# FPGA_IO_3.net
KiCad netlist of a schematic drawn in Altium Designer
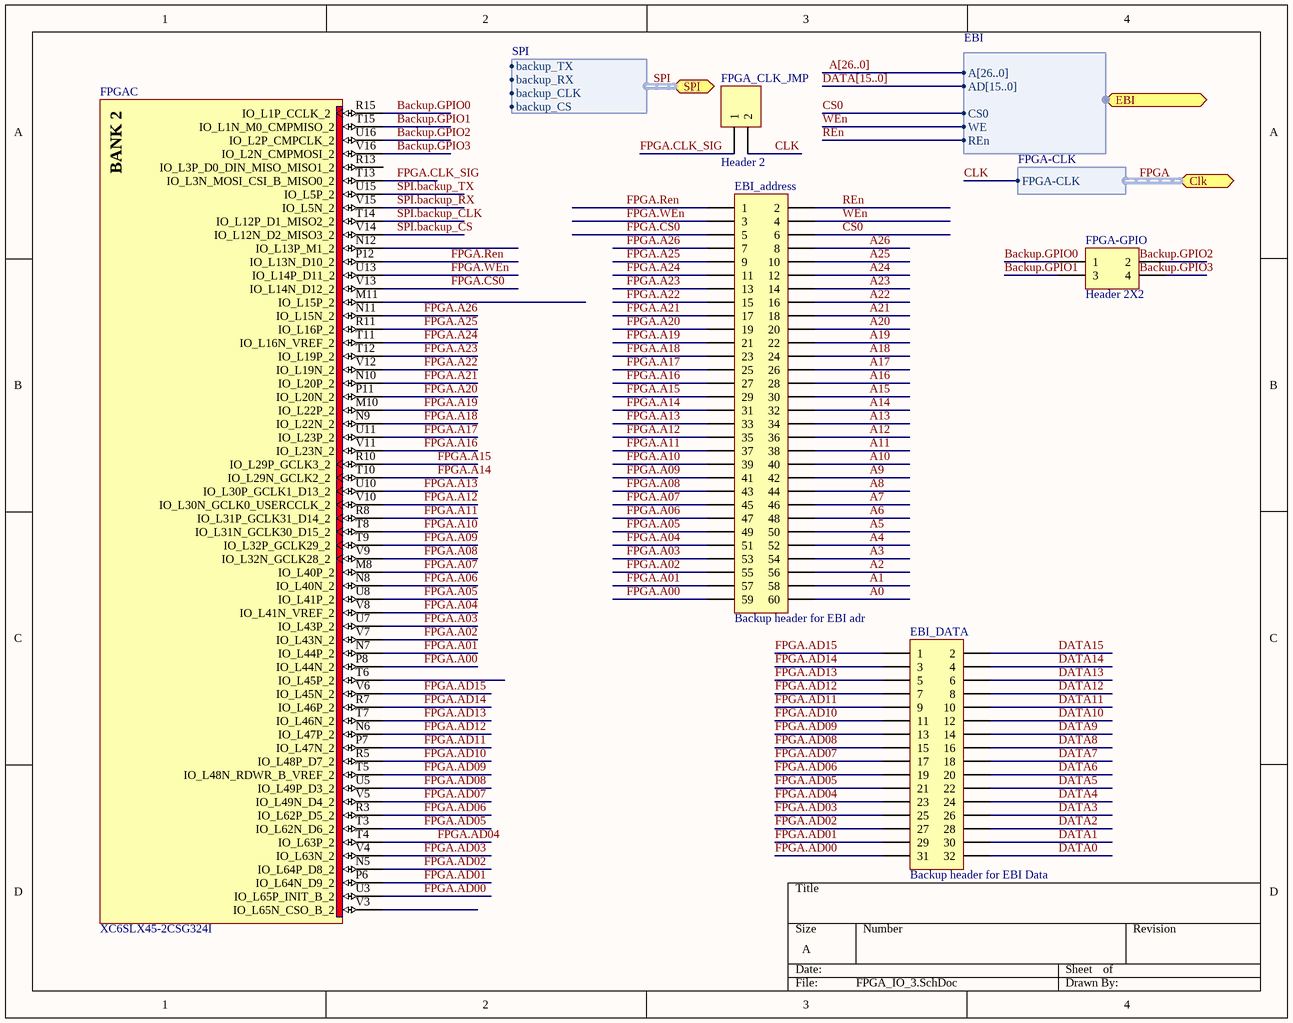
[diagram p0: FPGA_IO_3.SchDoc]

(export (version "E")
  (design (tool "Eeschema 10.0.6"))
  (components
    (comp (ref "EBI_address")
      (value "Backup header for EBI adr")
      (footprint "HDR2X30")
      (description "Header, 30-Pin, Dual row")
      (fields (field (name "PUBLISHER") "Altium Limited"))
      (libsource (lib "Miscellaneous Connectors") (part "Header 30X2"))
    )
    (comp (ref "EBI_DATA")
      (value "Backup header for EBI Data")
      (footprint "HDR2X16")
      (description "Header, 16-Pin, Dual row")
      (fields (field (name "PUBLISHER") "Altium Limited"))
      (libsource (lib "Miscellaneous Connectors") (part "Header 16X2"))
    )
    (comp (ref "FPGA")
      (value "XC6SLX45-2CSG324I")
      (footprint "CSG324")
      (libsource (lib "Altium Content Vault") (part "CMP-0067-00402-1"))
    )
    (comp (ref "FPGA-GPIO")
      (value "Header 2X2")
      (footprint "HDR2X2")
      (description "Header, 2-Pin, Dual row")
      (fields (field (name "PUBLISHER") "Altium Limited"))
      (libsource (lib "Miscellaneous Connectors") (part "Header 2X2"))
    )
    (comp (ref "FPGA_CLK_JMP")
      (value "Header 2")
      (footprint "HDR1X2")
      (description "Header, 2-Pin")
      (fields (field (name "PUBLISHER") "Altium Limited"))
      (libsource (lib "Miscellaneous Connectors") (part "Header 2"))
    )
  )
  (nets
    (net (code "4") (name "/A0") (class "Default")
      (node (ref "EBI_address") (pin "60") (pinfunction "60_60") (pintype "passive"))
    )
    (net (code "5") (name "/A1") (class "Default")
      (node (ref "EBI_address") (pin "58") (pinfunction "58_58") (pintype "passive"))
    )
    (net (code "6") (name "/A2") (class "Default")
      (node (ref "EBI_address") (pin "56") (pinfunction "56_56") (pintype "passive"))
    )
    (net (code "7") (name "/A3") (class "Default")
      (node (ref "EBI_address") (pin "54") (pinfunction "54_54") (pintype "passive"))
    )
    (net (code "8") (name "/A4") (class "Default")
      (node (ref "EBI_address") (pin "52") (pinfunction "52_52") (pintype "passive"))
    )
    (net (code "9") (name "/A5") (class "Default")
      (node (ref "EBI_address") (pin "50") (pinfunction "50_50") (pintype "passive"))
    )
    (net (code "10") (name "/A6") (class "Default")
      (node (ref "EBI_address") (pin "48") (pinfunction "48_48") (pintype "passive"))
    )
    (net (code "11") (name "/A7") (class "Default")
      (node (ref "EBI_address") (pin "46") (pinfunction "46_46") (pintype "passive"))
    )
    (net (code "12") (name "/A8") (class "Default")
      (node (ref "EBI_address") (pin "44") (pinfunction "44_44") (pintype "passive"))
    )
    (net (code "13") (name "/A9") (class "Default")
      (node (ref "EBI_address") (pin "42") (pinfunction "42_42") (pintype "passive"))
    )
    (net (code "14") (name "/A10") (class "Default")
      (node (ref "EBI_address") (pin "40") (pinfunction "40_40") (pintype "passive"))
    )
    (net (code "15") (name "/A11") (class "Default")
      (node (ref "EBI_address") (pin "38") (pinfunction "38_38") (pintype "passive"))
    )
    (net (code "16") (name "/A12") (class "Default")
      (node (ref "EBI_address") (pin "36") (pinfunction "36_36") (pintype "passive"))
    )
    (net (code "17") (name "/A13") (class "Default")
      (node (ref "EBI_address") (pin "34") (pinfunction "34_34") (pintype "passive"))
    )
    (net (code "18") (name "/A14") (class "Default")
      (node (ref "EBI_address") (pin "32") (pinfunction "32_32") (pintype "passive"))
    )
    (net (code "19") (name "/A15") (class "Default")
      (node (ref "EBI_address") (pin "30") (pinfunction "30_30") (pintype "passive"))
    )
    (net (code "20") (name "/A16") (class "Default")
      (node (ref "EBI_address") (pin "28") (pinfunction "28_28") (pintype "passive"))
    )
    (net (code "21") (name "/A17") (class "Default")
      (node (ref "EBI_address") (pin "26") (pinfunction "26_26") (pintype "passive"))
    )
    (net (code "22") (name "/A18") (class "Default")
      (node (ref "EBI_address") (pin "24") (pinfunction "24_24") (pintype "passive"))
    )
    (net (code "23") (name "/A19") (class "Default")
      (node (ref "EBI_address") (pin "22") (pinfunction "22_22") (pintype "passive"))
    )
    (net (code "24") (name "/A20") (class "Default")
      (node (ref "EBI_address") (pin "20") (pinfunction "20_20") (pintype "passive"))
    )
    (net (code "25") (name "/A21") (class "Default")
      (node (ref "EBI_address") (pin "18") (pinfunction "18_18") (pintype "passive"))
    )
    (net (code "26") (name "/A22") (class "Default")
      (node (ref "EBI_address") (pin "16") (pinfunction "16_16") (pintype "passive"))
    )
    (net (code "27") (name "/A23") (class "Default")
      (node (ref "EBI_address") (pin "14") (pinfunction "14_14") (pintype "passive"))
    )
    (net (code "28") (name "/A24") (class "Default")
      (node (ref "EBI_address") (pin "12") (pinfunction "12_12") (pintype "passive"))
    )
    (net (code "29") (name "/A25") (class "Default")
      (node (ref "EBI_address") (pin "10") (pinfunction "10_10") (pintype "passive"))
    )
    (net (code "30") (name "/A26") (class "Default")
      (node (ref "EBI_address") (pin "8") (pinfunction "8_8") (pintype "passive"))
    )
    (net (code "31") (name "/Backup.GPIO0") (class "Default")
      (node (ref "FPGA") (pin "R15") (pinfunction "IO_L1P_CCLK_2_R15") (pintype "bidirectional"))
      (node (ref "FPGA-GPIO") (pin "1") (pinfunction "1_1") (pintype "passive"))
    )
    (net (code "32") (name "/Backup.GPIO1") (class "Default")
      (node (ref "FPGA") (pin "T15") (pinfunction "IO_L1N_M0_CMPMISO_2_T15") (pintype "bidirectional"))
      (node (ref "FPGA-GPIO") (pin "3") (pinfunction "3_3") (pintype "passive"))
    )
    (net (code "33") (name "/Backup.GPIO2") (class "Default")
      (node (ref "FPGA") (pin "U16") (pinfunction "IO_L2P_CMPCLK_2_U16") (pintype "bidirectional"))
    )
    (net (code "34") (name "/Backup.GPIO3") (class "Default")
      (node (ref "FPGA") (pin "V16") (pinfunction "IO_L2N_CMPMOSI_2_V16") (pintype "bidirectional"))
    )
    (net (code "35") (name "/CLK") (class "Default")
      (node (ref "FPGA_CLK_JMP") (pin "2") (pinfunction "2_2") (pintype "passive"))
    )
    (net (code "36") (name "/CS0") (class "Default")
      (node (ref "EBI_address") (pin "6") (pinfunction "6_6") (pintype "passive"))
    )
    (net (code "37") (name "/DATA0") (class "Default")
      (node (ref "EBI_DATA") (pin "32") (pinfunction "32_32") (pintype "passive"))
    )
    (net (code "38") (name "/DATA1") (class "Default")
      (node (ref "EBI_DATA") (pin "30") (pinfunction "30_30") (pintype "passive"))
    )
    (net (code "39") (name "/DATA2") (class "Default")
      (node (ref "EBI_DATA") (pin "28") (pinfunction "28_28") (pintype "passive"))
    )
    (net (code "40") (name "/DATA3") (class "Default")
      (node (ref "EBI_DATA") (pin "26") (pinfunction "26_26") (pintype "passive"))
    )
    (net (code "41") (name "/DATA4") (class "Default")
      (node (ref "EBI_DATA") (pin "24") (pinfunction "24_24") (pintype "passive"))
    )
    (net (code "42") (name "/DATA5") (class "Default")
      (node (ref "EBI_DATA") (pin "22") (pinfunction "22_22") (pintype "passive"))
    )
    (net (code "43") (name "/DATA6") (class "Default")
      (node (ref "EBI_DATA") (pin "20") (pinfunction "20_20") (pintype "passive"))
    )
    (net (code "44") (name "/DATA7") (class "Default")
      (node (ref "EBI_DATA") (pin "18") (pinfunction "18_18") (pintype "passive"))
    )
    (net (code "45") (name "/DATA8") (class "Default")
      (node (ref "EBI_DATA") (pin "16") (pinfunction "16_16") (pintype "passive"))
    )
    (net (code "46") (name "/DATA9") (class "Default")
      (node (ref "EBI_DATA") (pin "14") (pinfunction "14_14") (pintype "passive"))
    )
    (net (code "47") (name "/DATA10") (class "Default")
      (node (ref "EBI_DATA") (pin "12") (pinfunction "12_12") (pintype "passive"))
    )
    (net (code "48") (name "/DATA11") (class "Default")
      (node (ref "EBI_DATA") (pin "10") (pinfunction "10_10") (pintype "passive"))
    )
    (net (code "49") (name "/DATA12") (class "Default")
      (node (ref "EBI_DATA") (pin "8") (pinfunction "8_8") (pintype "passive"))
    )
    (net (code "50") (name "/DATA13") (class "Default")
      (node (ref "EBI_DATA") (pin "6") (pinfunction "6_6") (pintype "passive"))
    )
    (net (code "51") (name "/DATA14") (class "Default")
      (node (ref "EBI_DATA") (pin "4") (pinfunction "4_4") (pintype "passive"))
    )
    (net (code "52") (name "/DATA15") (class "Default")
      (node (ref "EBI_DATA") (pin "2") (pinfunction "2_2") (pintype "passive"))
    )
    (net (code "55") (name "/FPGA.A00") (class "Default")
      (node (ref "EBI_address") (pin "59") (pinfunction "59_59") (pintype "passive"))
      (node (ref "FPGA") (pin "P8") (pinfunction "IO_L44N_2_P8") (pintype "bidirectional"))
    )
    (net (code "56") (name "/FPGA.A01") (class "Default")
      (node (ref "EBI_address") (pin "57") (pinfunction "57_57") (pintype "passive"))
      (node (ref "FPGA") (pin "N7") (pinfunction "IO_L44P_2_N7") (pintype "bidirectional"))
    )
    (net (code "57") (name "/FPGA.A02") (class "Default")
      (node (ref "EBI_address") (pin "55") (pinfunction "55_55") (pintype "passive"))
      (node (ref "FPGA") (pin "V7") (pinfunction "IO_L43N_2_V7") (pintype "bidirectional"))
    )
    (net (code "58") (name "/FPGA.A03") (class "Default")
      (node (ref "EBI_address") (pin "53") (pinfunction "53_53") (pintype "passive"))
      (node (ref "FPGA") (pin "U7") (pinfunction "IO_L43P_2_U7") (pintype "bidirectional"))
    )
    (net (code "59") (name "/FPGA.A04") (class "Default")
      (node (ref "EBI_address") (pin "51") (pinfunction "51_51") (pintype "passive"))
      (node (ref "FPGA") (pin "V8") (pinfunction "IO_L41N_VREF_2_V8") (pintype "bidirectional"))
    )
    (net (code "60") (name "/FPGA.A05") (class "Default")
      (node (ref "EBI_address") (pin "49") (pinfunction "49_49") (pintype "passive"))
      (node (ref "FPGA") (pin "U8") (pinfunction "IO_L41P_2_U8") (pintype "bidirectional"))
    )
    (net (code "61") (name "/FPGA.A06") (class "Default")
      (node (ref "EBI_address") (pin "47") (pinfunction "47_47") (pintype "passive"))
      (node (ref "FPGA") (pin "N8") (pinfunction "IO_L40N_2_N8") (pintype "bidirectional"))
    )
    (net (code "62") (name "/FPGA.A07") (class "Default")
      (node (ref "EBI_address") (pin "45") (pinfunction "45_45") (pintype "passive"))
      (node (ref "FPGA") (pin "M8") (pinfunction "IO_L40P_2_M8") (pintype "bidirectional"))
    )
    (net (code "63") (name "/FPGA.A08") (class "Default")
      (node (ref "EBI_address") (pin "43") (pinfunction "43_43") (pintype "passive"))
      (node (ref "FPGA") (pin "V9") (pinfunction "IO_L32N_GCLK28_2_V9") (pintype "bidirectional"))
    )
    (net (code "64") (name "/FPGA.A09") (class "Default")
      (node (ref "EBI_address") (pin "41") (pinfunction "41_41") (pintype "passive"))
      (node (ref "FPGA") (pin "T9") (pinfunction "IO_L32P_GCLK29_2_T9") (pintype "bidirectional"))
    )
    (net (code "65") (name "/FPGA.A10") (class "Default")
      (node (ref "EBI_address") (pin "39") (pinfunction "39_39") (pintype "passive"))
      (node (ref "FPGA") (pin "T8") (pinfunction "IO_L31N_GCLK30_D15_2_T8") (pintype "bidirectional"))
    )
    (net (code "66") (name "/FPGA.A11") (class "Default")
      (node (ref "EBI_address") (pin "37") (pinfunction "37_37") (pintype "passive"))
      (node (ref "FPGA") (pin "R8") (pinfunction "IO_L31P_GCLK31_D14_2_R8") (pintype "bidirectional"))
    )
    (net (code "67") (name "/FPGA.A12") (class "Default")
      (node (ref "EBI_address") (pin "35") (pinfunction "35_35") (pintype "passive"))
      (node (ref "FPGA") (pin "V10") (pinfunction "IO_L30N_GCLK0_USERCCLK_2_V10") (pintype "bidirectional"))
    )
    (net (code "68") (name "/FPGA.A13") (class "Default")
      (node (ref "EBI_address") (pin "33") (pinfunction "33_33") (pintype "passive"))
      (node (ref "FPGA") (pin "U10") (pinfunction "IO_L30P_GCLK1_D13_2_U10") (pintype "bidirectional"))
    )
    (net (code "69") (name "/FPGA.A14") (class "Default")
      (node (ref "EBI_address") (pin "31") (pinfunction "31_31") (pintype "passive"))
      (node (ref "FPGA") (pin "T10") (pinfunction "IO_L29N_GCLK2_2_T10") (pintype "bidirectional"))
    )
    (net (code "70") (name "/FPGA.A15") (class "Default")
      (node (ref "EBI_address") (pin "29") (pinfunction "29_29") (pintype "passive"))
      (node (ref "FPGA") (pin "R10") (pinfunction "IO_L29P_GCLK3_2_R10") (pintype "bidirectional"))
    )
    (net (code "71") (name "/FPGA.A16") (class "Default")
      (node (ref "EBI_address") (pin "27") (pinfunction "27_27") (pintype "passive"))
      (node (ref "FPGA") (pin "V11") (pinfunction "IO_L23N_2_V11") (pintype "bidirectional"))
    )
    (net (code "72") (name "/FPGA.A17") (class "Default")
      (node (ref "EBI_address") (pin "25") (pinfunction "25_25") (pintype "passive"))
      (node (ref "FPGA") (pin "U11") (pinfunction "IO_L23P_2_U11") (pintype "bidirectional"))
    )
    (net (code "73") (name "/FPGA.A18") (class "Default")
      (node (ref "EBI_address") (pin "23") (pinfunction "23_23") (pintype "passive"))
      (node (ref "FPGA") (pin "N9") (pinfunction "IO_L22N_2_N9") (pintype "bidirectional"))
    )
    (net (code "74") (name "/FPGA.A19") (class "Default")
      (node (ref "EBI_address") (pin "21") (pinfunction "21_21") (pintype "passive"))
      (node (ref "FPGA") (pin "M10") (pinfunction "IO_L22P_2_M10") (pintype "bidirectional"))
    )
    (net (code "75") (name "/FPGA.A20") (class "Default")
      (node (ref "EBI_address") (pin "19") (pinfunction "19_19") (pintype "passive"))
      (node (ref "FPGA") (pin "P11") (pinfunction "IO_L20N_2_P11") (pintype "bidirectional"))
    )
    (net (code "76") (name "/FPGA.A21") (class "Default")
      (node (ref "EBI_address") (pin "17") (pinfunction "17_17") (pintype "passive"))
      (node (ref "FPGA") (pin "N10") (pinfunction "IO_L20P_2_N10") (pintype "bidirectional"))
    )
    (net (code "77") (name "/FPGA.A22") (class "Default")
      (node (ref "EBI_address") (pin "15") (pinfunction "15_15") (pintype "passive"))
      (node (ref "FPGA") (pin "V12") (pinfunction "IO_L19N_2_V12") (pintype "bidirectional"))
    )
    (net (code "78") (name "/FPGA.A23") (class "Default")
      (node (ref "EBI_address") (pin "13") (pinfunction "13_13") (pintype "passive"))
      (node (ref "FPGA") (pin "T12") (pinfunction "IO_L19P_2_T12") (pintype "bidirectional"))
    )
    (net (code "79") (name "/FPGA.A24") (class "Default")
      (node (ref "EBI_address") (pin "11") (pinfunction "11_11") (pintype "passive"))
      (node (ref "FPGA") (pin "T11") (pinfunction "IO_L16N_VREF_2_T11") (pintype "bidirectional"))
    )
    (net (code "80") (name "/FPGA.A25") (class "Default")
      (node (ref "EBI_address") (pin "9") (pinfunction "9_9") (pintype "passive"))
      (node (ref "FPGA") (pin "R11") (pinfunction "IO_L16P_2_R11") (pintype "bidirectional"))
    )
    (net (code "81") (name "/FPGA.A26") (class "Default")
      (node (ref "EBI_address") (pin "7") (pinfunction "7_7") (pintype "passive"))
      (node (ref "FPGA") (pin "N11") (pinfunction "IO_L15N_2_N11") (pintype "bidirectional"))
    )
    (net (code "82") (name "/FPGA.AD00") (class "Default")
      (node (ref "EBI_DATA") (pin "31") (pinfunction "31_31") (pintype "passive"))
      (node (ref "FPGA") (pin "U3") (pinfunction "IO_L65P_INIT_B_2_U3") (pintype "bidirectional"))
    )
    (net (code "83") (name "/FPGA.AD01") (class "Default")
      (node (ref "EBI_DATA") (pin "29") (pinfunction "29_29") (pintype "passive"))
      (node (ref "FPGA") (pin "P6") (pinfunction "IO_L64N_D9_2_P6") (pintype "bidirectional"))
    )
    (net (code "84") (name "/FPGA.AD02") (class "Default")
      (node (ref "EBI_DATA") (pin "27") (pinfunction "27_27") (pintype "passive"))
      (node (ref "FPGA") (pin "N5") (pinfunction "IO_L64P_D8_2_N5") (pintype "bidirectional"))
    )
    (net (code "85") (name "/FPGA.AD03") (class "Default")
      (node (ref "EBI_DATA") (pin "25") (pinfunction "25_25") (pintype "passive"))
      (node (ref "FPGA") (pin "V4") (pinfunction "IO_L63N_2_V4") (pintype "bidirectional"))
    )
    (net (code "86") (name "/FPGA.AD04") (class "Default")
      (node (ref "EBI_DATA") (pin "23") (pinfunction "23_23") (pintype "passive"))
      (node (ref "FPGA") (pin "T4") (pinfunction "IO_L63P_2_T4") (pintype "bidirectional"))
    )
    (net (code "87") (name "/FPGA.AD05") (class "Default")
      (node (ref "EBI_DATA") (pin "21") (pinfunction "21_21") (pintype "passive"))
      (node (ref "FPGA") (pin "T3") (pinfunction "IO_L62N_D6_2_T3") (pintype "bidirectional"))
    )
    (net (code "88") (name "/FPGA.AD06") (class "Default")
      (node (ref "EBI_DATA") (pin "19") (pinfunction "19_19") (pintype "passive"))
      (node (ref "FPGA") (pin "R3") (pinfunction "IO_L62P_D5_2_R3") (pintype "bidirectional"))
    )
    (net (code "89") (name "/FPGA.AD07") (class "Default")
      (node (ref "EBI_DATA") (pin "17") (pinfunction "17_17") (pintype "passive"))
      (node (ref "FPGA") (pin "V5") (pinfunction "IO_L49N_D4_2_V5") (pintype "bidirectional"))
    )
    (net (code "90") (name "/FPGA.AD08") (class "Default")
      (node (ref "EBI_DATA") (pin "15") (pinfunction "15_15") (pintype "passive"))
      (node (ref "FPGA") (pin "U5") (pinfunction "IO_L49P_D3_2_U5") (pintype "bidirectional"))
    )
    (net (code "91") (name "/FPGA.AD09") (class "Default")
      (node (ref "EBI_DATA") (pin "13") (pinfunction "13_13") (pintype "passive"))
      (node (ref "FPGA") (pin "T5") (pinfunction "IO_L48N_RDWR_B_VREF_2_T5") (pintype "bidirectional"))
    )
    (net (code "92") (name "/FPGA.AD10") (class "Default")
      (node (ref "EBI_DATA") (pin "11") (pinfunction "11_11") (pintype "passive"))
      (node (ref "FPGA") (pin "R5") (pinfunction "IO_L48P_D7_2_R5") (pintype "bidirectional"))
    )
    (net (code "93") (name "/FPGA.AD11") (class "Default")
      (node (ref "EBI_DATA") (pin "9") (pinfunction "9_9") (pintype "passive"))
      (node (ref "FPGA") (pin "P7") (pinfunction "IO_L47N_2_P7") (pintype "bidirectional"))
    )
    (net (code "94") (name "/FPGA.AD12") (class "Default")
      (node (ref "EBI_DATA") (pin "7") (pinfunction "7_7") (pintype "passive"))
      (node (ref "FPGA") (pin "N6") (pinfunction "IO_L47P_2_N6") (pintype "bidirectional"))
    )
    (net (code "95") (name "/FPGA.AD13") (class "Default")
      (node (ref "EBI_DATA") (pin "5") (pinfunction "5_5") (pintype "passive"))
      (node (ref "FPGA") (pin "T7") (pinfunction "IO_L46N_2_T7") (pintype "bidirectional"))
    )
    (net (code "96") (name "/FPGA.AD14") (class "Default")
      (node (ref "EBI_DATA") (pin "3") (pinfunction "3_3") (pintype "passive"))
      (node (ref "FPGA") (pin "R7") (pinfunction "IO_L46P_2_R7") (pintype "bidirectional"))
    )
    (net (code "97") (name "/FPGA.AD15") (class "Default")
      (node (ref "EBI_DATA") (pin "1") (pinfunction "1_1") (pintype "passive"))
      (node (ref "FPGA") (pin "V6") (pinfunction "IO_L45N_2_V6") (pintype "bidirectional"))
    )
    (net (code "98") (name "/FPGA.CLK_SIG") (class "Default")
      (node (ref "FPGA") (pin "T13") (pinfunction "IO_L3N_MOSI_CSI_B_MISO0_2_T13") (pintype "bidirectional"))
      (node (ref "FPGA_CLK_JMP") (pin "1") (pinfunction "1_1") (pintype "passive"))
    )
    (net (code "99") (name "/FPGA.CS0") (class "Default")
      (node (ref "EBI_address") (pin "5") (pinfunction "5_5") (pintype "passive"))
      (node (ref "FPGA") (pin "V13") (pinfunction "IO_L14N_D12_2_V13") (pintype "bidirectional"))
    )
    (net (code "100") (name "/FPGA.Ren") (class "Default")
      (node (ref "EBI_address") (pin "1") (pinfunction "1_1") (pintype "passive"))
      (node (ref "FPGA") (pin "P12") (pinfunction "IO_L13N_D10_2_P12") (pintype "bidirectional"))
    )
    (net (code "101") (name "/FPGA.WEn") (class "Default")
      (node (ref "EBI_address") (pin "3") (pinfunction "3_3") (pintype "passive"))
      (node (ref "FPGA") (pin "U13") (pinfunction "IO_L14P_D11_2_U13") (pintype "bidirectional"))
    )
    (net (code "103") (name "/REn") (class "Default")
      (node (ref "EBI_address") (pin "2") (pinfunction "2_2") (pintype "passive"))
    )
    (net (code "104") (name "/SPI.backup_CLK") (class "Default")
      (node (ref "FPGA") (pin "T14") (pinfunction "IO_L12P_D1_MISO2_2_T14") (pintype "bidirectional"))
    )
    (net (code "105") (name "/SPI.backup_CS") (class "Default")
      (node (ref "FPGA") (pin "V14") (pinfunction "IO_L12N_D2_MISO3_2_V14") (pintype "bidirectional"))
    )
    (net (code "106") (name "/SPI.backup_RX") (class "Default")
      (node (ref "FPGA") (pin "V15") (pinfunction "IO_L5N_2_V15") (pintype "bidirectional"))
    )
    (net (code "107") (name "/SPI.backup_TX") (class "Default")
      (node (ref "FPGA") (pin "U15") (pinfunction "IO_L5P_2_U15") (pintype "bidirectional"))
    )
    (net (code "109") (name "/WEn") (class "Default")
      (node (ref "EBI_address") (pin "4") (pinfunction "4_4") (pintype "passive"))
    )
    (net (code "111") (name "unconnected-(FPGA-GPIO-Pad2)") (class "Default")
      (node (ref "FPGA-GPIO") (pin "2") (pinfunction "2_2") (pintype "passive"))
    )
    (net (code "112") (name "unconnected-(FPGA-GPIO-Pad4)") (class "Default")
      (node (ref "FPGA-GPIO") (pin "4") (pinfunction "4_4") (pintype "passive"))
    )
    (net (code "113") (name "unconnected-(FPGAC-IO_L3P_D0_DIN_MISO_MISO1_2-PadR13)") (class "Default")
      (node (ref "FPGA") (pin "R13") (pinfunction "IO_L3P_D0_DIN_MISO_MISO1_2_R13") (pintype "bidirectional"))
    )
    (net (code "114") (name "unconnected-(FPGAC-IO_L13P_M1_2-PadN12)") (class "Default")
      (node (ref "FPGA") (pin "N12") (pinfunction "IO_L13P_M1_2_N12") (pintype "bidirectional"))
    )
    (net (code "115") (name "unconnected-(FPGAC-IO_L15P_2-PadM11)") (class "Default")
      (node (ref "FPGA") (pin "M11") (pinfunction "IO_L15P_2_M11") (pintype "bidirectional"))
    )
    (net (code "116") (name "unconnected-(FPGAC-IO_L45P_2-PadT6)") (class "Default")
      (node (ref "FPGA") (pin "T6") (pinfunction "IO_L45P_2_T6") (pintype "bidirectional"))
    )
    (net (code "117") (name "unconnected-(FPGAC-IO_L65N_CSO_B_2-PadV3)") (class "Default")
      (node (ref "FPGA") (pin "V3") (pinfunction "IO_L65N_CSO_B_2_V3") (pintype "bidirectional"))
    )
  )
)
